# Perfboard_Connection.net
KiCad netlist of a schematic drawn in Altium Designer
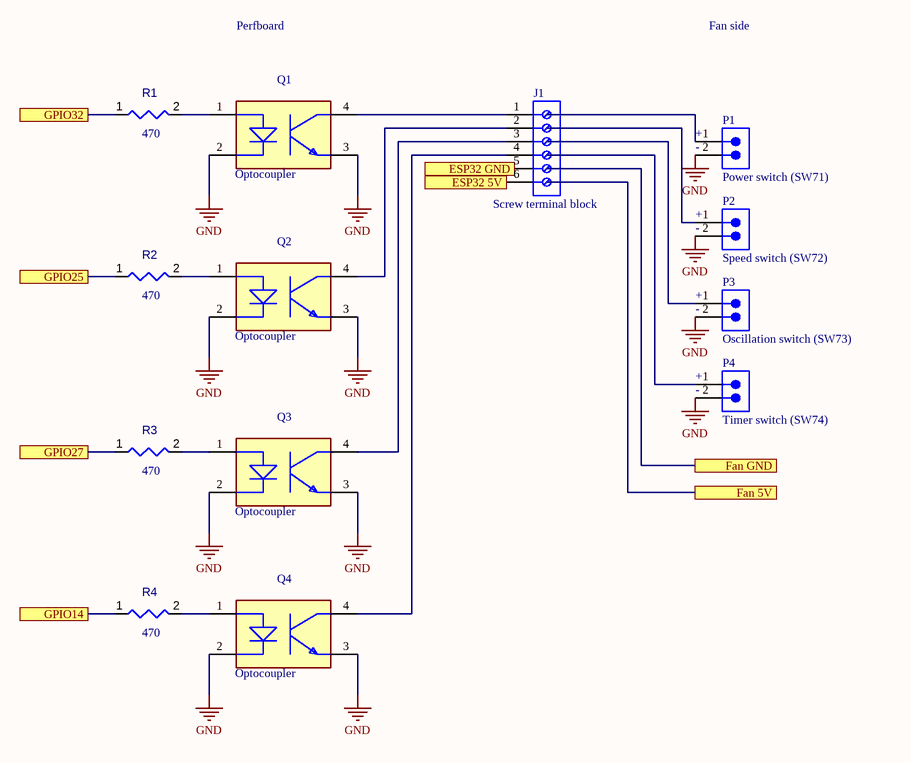
[diagram p0: Perfboard_Connection.SchDoc]

(export (version "E")
  (design (tool "Eeschema 10.0.6"))
  (components
    (comp (ref "J1")
      (value "Screw terminal block")
      (footprint "691132700006")
      (description "Terminal Block, 5MM Pitch, Vertical, Pressure Clamp, 30-12 AWG, 6 Pins, Gry")
      (fields (field (name "VOLTAGE") "300V"))
      (libsource (lib "Altium Content Vault") (part "TBL - 1R - 06P - Screw"))
    )
    (comp (ref "P1")
      (value "Power switch (SW71)")
      (footprint "691701500002B")
      (description "Terminal Block, 5.08MM, Open Vertical Pcb Header, Thr Type, 2 Pins")
      (libsource (lib "Altium Content Vault") (part "TBL - 1R - 02P - Male"))
    )
    (comp (ref "P2")
      (value "Speed switch (SW72)")
      (footprint "691701500002B")
      (description "Terminal Block, 5.08MM, Open Vertical Pcb Header, Thr Type, 2 Pins")
      (libsource (lib "Altium Content Vault") (part "TBL - 1R - 02P - Male"))
    )
    (comp (ref "P3")
      (value "Oscillation switch (SW73)")
      (footprint "691701500002B")
      (description "Terminal Block, 5.08MM, Open Vertical Pcb Header, Thr Type, 2 Pins")
      (libsource (lib "Altium Content Vault") (part "TBL - 1R - 02P - Male"))
    )
    (comp (ref "P4")
      (value "Timer switch (SW74)")
      (footprint "691701500002B")
      (description "Terminal Block, 5.08MM, Open Vertical Pcb Header, Thr Type, 2 Pins")
      (libsource (lib "Altium Content Vault") (part "TBL - 1R - 02P - Male"))
    )
    (comp (ref "Q1")
      (value "Optocoupler")
      (footprint "FP-PC817X1J000F-MFG")
      (description "OPTOISOLATOR 5KV TRANS 4DIP")
      (libsource (lib "Altium Content Vault") (part "8d9d817270a4e8f0d794346117f6aa3"))
    )
    (comp (ref "Q2")
      (value "Optocoupler")
      (footprint "FP-PC817X1J000F-MFG")
      (description "OPTOISOLATOR 5KV TRANS 4DIP")
      (libsource (lib "Altium Content Vault") (part "8d9d817270a4e8f0d794346117f6aa3"))
    )
    (comp (ref "Q3")
      (value "Optocoupler")
      (footprint "FP-PC817X1J000F-MFG")
      (description "OPTOISOLATOR 5KV TRANS 4DIP")
      (libsource (lib "Altium Content Vault") (part "8d9d817270a4e8f0d794346117f6aa3"))
    )
    (comp (ref "Q4")
      (value "Optocoupler")
      (footprint "FP-PC817X1J000F-MFG")
      (description "OPTOISOLATOR 5KV TRANS 4DIP")
      (libsource (lib "Altium Content Vault") (part "8d9d817270a4e8f0d794346117f6aa3"))
    )
    (comp (ref "R1")
      (value "470")
      (footprint "RESC0805(2012)_L")
      (description "Chip Resistor, 470 Ohms, +/-5%, 125 mW, -55 to 155 degC, 0805")
      (fields (field (name "TOLERANCE") "5%") (field (name "POWER") "125mW"))
      (libsource (lib "Vinolia - KU Leuven") (part "RES-2"))
    )
    (comp (ref "R2")
      (value "470")
      (footprint "RESC0805(2012)_L")
      (description "Chip Resistor, 470 Ohms, +/-5%, 125 mW, -55 to 155 degC, 0805")
      (fields (field (name "TOLERANCE") "5%") (field (name "POWER") "125mW"))
      (libsource (lib "Vinolia - KU Leuven") (part "RES-2"))
    )
    (comp (ref "R3")
      (value "470")
      (footprint "RESC0805(2012)_L")
      (description "Chip Resistor, 470 Ohms, +/-5%, 125 mW, -55 to 155 degC, 0805")
      (fields (field (name "TOLERANCE") "5%") (field (name "POWER") "125mW"))
      (libsource (lib "Vinolia - KU Leuven") (part "RES-2"))
    )
    (comp (ref "R4")
      (value "470")
      (footprint "RESC0805(2012)_L")
      (description "Chip Resistor, 470 Ohms, +/-5%, 125 mW, -55 to 155 degC, 0805")
      (fields (field (name "TOLERANCE") "5%") (field (name "POWER") "125mW"))
      (libsource (lib "Vinolia - KU Leuven") (part "RES-2"))
    )
  )
  (nets
    (net (code "1") (name "/ESP32 5V") (class "Default")
      (node (ref "J1") (pin "6") (pinfunction "6_6") (pintype "passive"))
    )
    (net (code "5") (name "/GPIO14") (class "Default")
      (node (ref "R4") (pin "1") (pinfunction "1_1") (pintype "passive"))
    )
    (net (code "6") (name "/GPIO25") (class "Default")
      (node (ref "R2") (pin "1") (pinfunction "1_1") (pintype "passive"))
    )
    (net (code "7") (name "/GPIO27") (class "Default")
      (node (ref "R3") (pin "1") (pinfunction "1_1") (pintype "passive"))
    )
    (net (code "8") (name "/GPIO32") (class "Default")
      (node (ref "R1") (pin "1") (pinfunction "1_1") (pintype "passive"))
    )
    (net (code "9") (name "GND") (class "Default")
      (node (ref "P1") (pin "2") (pinfunction "2_2") (pintype "passive"))
      (node (ref "P2") (pin "2") (pinfunction "2_2") (pintype "passive"))
      (node (ref "P3") (pin "2") (pinfunction "2_2") (pintype "passive"))
      (node (ref "P4") (pin "2") (pinfunction "2_2") (pintype "passive"))
      (node (ref "Q1") (pin "2") (pinfunction "C_2") (pintype "passive"))
      (node (ref "Q1") (pin "3") (pinfunction "E_3") (pintype "passive"))
      (node (ref "Q2") (pin "2") (pinfunction "C_2") (pintype "passive"))
      (node (ref "Q2") (pin "3") (pinfunction "E_3") (pintype "passive"))
      (node (ref "Q3") (pin "2") (pinfunction "C_2") (pintype "passive"))
      (node (ref "Q3") (pin "3") (pinfunction "E_3") (pintype "passive"))
      (node (ref "Q4") (pin "2") (pinfunction "C_2") (pintype "passive"))
      (node (ref "Q4") (pin "3") (pinfunction "E_3") (pintype "passive"))
    )
    (net (code "10") (name "Net-(J1-Pad1)") (class "Default")
      (node (ref "J1") (pin "1") (pinfunction "1_1") (pintype "passive"))
      (node (ref "Q1") (pin "4") (pinfunction "C_4") (pintype "passive"))
    )
    (net (code "11") (name "Net-(J1-Pad2)") (class "Default")
      (node (ref "J1") (pin "2") (pinfunction "2_2") (pintype "passive"))
      (node (ref "Q2") (pin "4") (pinfunction "C_4") (pintype "passive"))
    )
    (net (code "12") (name "Net-(J1-Pad3)") (class "Default")
      (node (ref "J1") (pin "3") (pinfunction "3_3") (pintype "passive"))
      (node (ref "Q3") (pin "4") (pinfunction "C_4") (pintype "passive"))
    )
    (net (code "13") (name "Net-(J1-Pad4)") (class "Default")
      (node (ref "J1") (pin "4") (pinfunction "4_4") (pintype "passive"))
      (node (ref "Q4") (pin "4") (pinfunction "C_4") (pintype "passive"))
    )
    (net (code "14") (name "Net-(Q1-A)") (class "Default")
      (node (ref "Q1") (pin "1") (pinfunction "A_1") (pintype "passive"))
      (node (ref "R1") (pin "2") (pinfunction "2_2") (pintype "passive"))
    )
    (net (code "15") (name "Net-(Q2-A)") (class "Default")
      (node (ref "Q2") (pin "1") (pinfunction "A_1") (pintype "passive"))
      (node (ref "R2") (pin "2") (pinfunction "2_2") (pintype "passive"))
    )
    (net (code "16") (name "Net-(Q3-A)") (class "Default")
      (node (ref "Q3") (pin "1") (pinfunction "A_1") (pintype "passive"))
      (node (ref "R3") (pin "2") (pinfunction "2_2") (pintype "passive"))
    )
    (net (code "17") (name "Net-(Q4-A)") (class "Default")
      (node (ref "Q4") (pin "1") (pinfunction "A_1") (pintype "passive"))
      (node (ref "R4") (pin "2") (pinfunction "2_2") (pintype "passive"))
    )
    (net (code "18") (name "unconnected-(J1-Pad5)") (class "Default")
      (node (ref "J1") (pin "5") (pinfunction "5_5") (pintype "passive"))
    )
    (net (code "19") (name "unconnected-(P1-Pad1)") (class "Default")
      (node (ref "P1") (pin "1") (pinfunction "1_1") (pintype "passive"))
    )
    (net (code "20") (name "unconnected-(P2-Pad1)") (class "Default")
      (node (ref "P2") (pin "1") (pinfunction "1_1") (pintype "passive"))
    )
    (net (code "21") (name "unconnected-(P3-Pad1)") (class "Default")
      (node (ref "P3") (pin "1") (pinfunction "1_1") (pintype "passive"))
    )
    (net (code "22") (name "unconnected-(P4-Pad1)") (class "Default")
      (node (ref "P4") (pin "1") (pinfunction "1_1") (pintype "passive"))
    )
  )
)
